# stepdrv.net
KiCad netlist of a schematic drawn in EAGLE
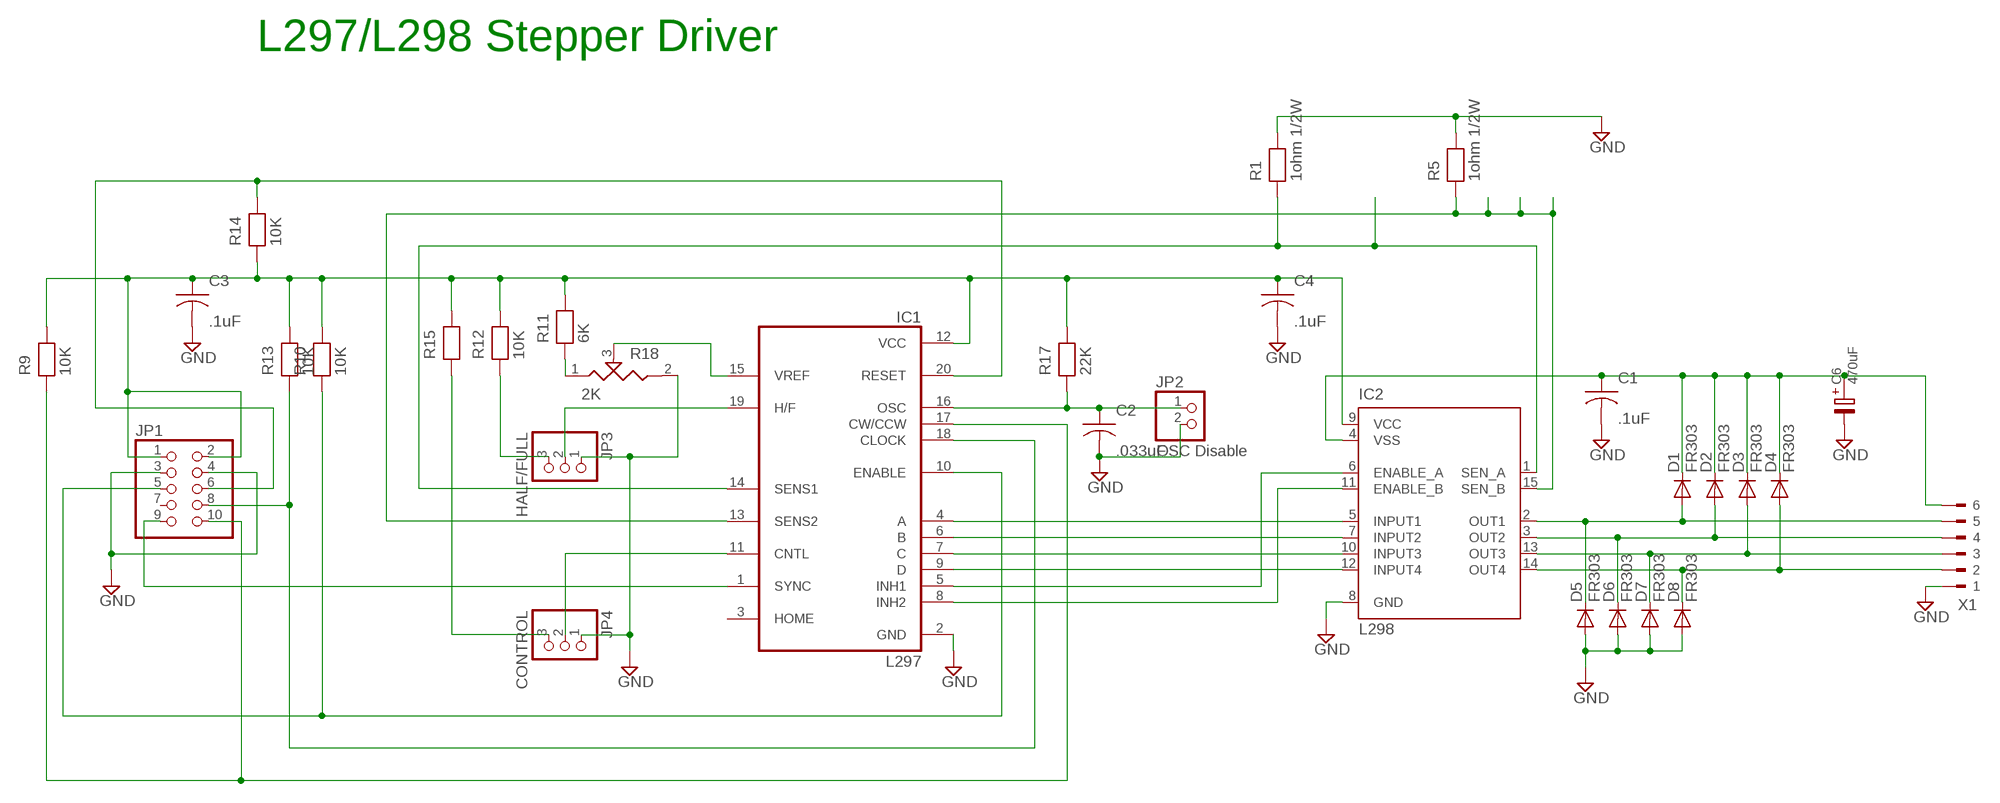
[diagram p0: schematic, sheet 1]

(export (version "E")
  (design (tool "Eeschema 10.0.6"))
  (components
    (comp (ref "C1")
      (value ".1uF")
      (footprint "eagle-import:C-5")
      (libsource (lib "eagle-import") (part "CAP-5"))
    )
    (comp (ref "C2")
      (value ".033uF")
      (footprint "eagle-import:C-5")
      (libsource (lib "eagle-import") (part "CAP-5"))
    )
    (comp (ref "C3")
      (value ".1uF")
      (footprint "eagle-import:C-5")
      (libsource (lib "eagle-import") (part "CAP-5"))
    )
    (comp (ref "C4")
      (value ".1uF")
      (footprint "eagle-import:C-5")
      (libsource (lib "eagle-import") (part "CAP-5"))
    )
    (comp (ref "C6")
      (value "470uF")
      (footprint "eagle-import:E5,0-12")
      (libsource (lib "eagle-import") (part "E5,0-12"))
    )
    (comp (ref "D1")
      (value "FR303")
      (footprint "eagle-import:DO201-15")
      (libsource (lib "eagle-import") (part "DIODE-DO201-15"))
    )
    (comp (ref "D2")
      (value "FR303")
      (footprint "eagle-import:DO201-15")
      (libsource (lib "eagle-import") (part "DIODE-DO201-15"))
    )
    (comp (ref "D3")
      (value "FR303")
      (footprint "eagle-import:DO201-15")
      (libsource (lib "eagle-import") (part "DIODE-DO201-15"))
    )
    (comp (ref "D4")
      (value "FR303")
      (footprint "eagle-import:DO201-15")
      (libsource (lib "eagle-import") (part "DIODE-DO201-15"))
    )
    (comp (ref "D5")
      (value "FR303")
      (footprint "eagle-import:DO201-15")
      (libsource (lib "eagle-import") (part "DIODE-DO201-15"))
    )
    (comp (ref "D6")
      (value "FR303")
      (footprint "eagle-import:DO201-15")
      (libsource (lib "eagle-import") (part "DIODE-DO201-15"))
    )
    (comp (ref "D7")
      (value "FR303")
      (footprint "eagle-import:DO201-15")
      (libsource (lib "eagle-import") (part "DIODE-DO201-15"))
    )
    (comp (ref "D8")
      (value "FR303")
      (footprint "eagle-import:DO201-15")
      (libsource (lib "eagle-import") (part "DIODE-DO201-15"))
    )
    (comp (ref "IC1")
      (value "L297")
      (footprint "eagle-import:DIL20")
      (libsource (lib "eagle-import") (part "L297"))
    )
    (comp (ref "IC2")
      (value "L298")
      (footprint "eagle-import:MULTIWATT-15")
      (libsource (lib "eagle-import") (part "L298"))
    )
    (comp (ref "JP1")
      (value "PINHD-2X5")
      (footprint "eagle-import:2X05")
      (libsource (lib "eagle-import") (part "PINHD-2X5"))
    )
    (comp (ref "JP2")
      (value "OSC Disable")
      (footprint "eagle-import:1X02")
      (libsource (lib "eagle-import") (part "PINHD-1X2"))
    )
    (comp (ref "JP3")
      (value "HALF/FULL")
      (footprint "eagle-import:1X03")
      (libsource (lib "eagle-import") (part "PINHD-1X3"))
    )
    (comp (ref "JP4")
      (value "CONTROL")
      (footprint "eagle-import:1X03")
      (libsource (lib "eagle-import") (part "PINHD-1X3"))
    )
    (comp (ref "R1")
      (value "1ohm 1/2W")
      (footprint "eagle-import:R-12,5")
      (libsource (lib "eagle-import") (part "RESEU-12,5"))
    )
    (comp (ref "R5")
      (value "1ohm 1/2W")
      (footprint "eagle-import:R-12,5")
      (libsource (lib "eagle-import") (part "RESEU-12,5"))
    )
    (comp (ref "R9")
      (value "10K")
      (footprint "eagle-import:R-10")
      (libsource (lib "eagle-import") (part "RESEU-10"))
    )
    (comp (ref "R10")
      (value "10K")
      (footprint "eagle-import:R-10")
      (libsource (lib "eagle-import") (part "RESEU-10"))
    )
    (comp (ref "R11")
      (value "6K")
      (footprint "eagle-import:R-10")
      (libsource (lib "eagle-import") (part "RESEU-10"))
    )
    (comp (ref "R12")
      (value "10K")
      (footprint "eagle-import:R-10")
      (libsource (lib "eagle-import") (part "RESEU-10"))
    )
    (comp (ref "R13")
      (value "10K")
      (footprint "eagle-import:R-10")
      (libsource (lib "eagle-import") (part "RESEU-10"))
    )
    (comp (ref "R14")
      (value "10K")
      (footprint "eagle-import:R-10")
      (libsource (lib "eagle-import") (part "RESEU-10"))
    )
    (comp (ref "R15")
      (value "RESEU-10")
      (footprint "eagle-import:R-10")
      (libsource (lib "eagle-import") (part "RESEU-10"))
    )
    (comp (ref "R17")
      (value "22K")
      (footprint "eagle-import:R-10")
      (libsource (lib "eagle-import") (part "RESEU-10"))
    )
    (comp (ref "R18")
      (value "2K")
      (footprint "eagle-import:PT-10S")
      (libsource (lib "eagle-import") (part "POTUS-S"))
    )
    (comp (ref "X1")
      (value "90-6")
      (footprint "eagle-import:90-6")
      (libsource (lib "eagle-import") (part "90-6"))
    )
  )
  (nets
    (net (code "1") (name "GND") (class "Default")
      (node (ref "C1") (pin "2") (pinfunction "2_2") (pintype "passive"))
      (node (ref "C2") (pin "2") (pinfunction "2_2") (pintype "passive"))
      (node (ref "C3") (pin "2") (pinfunction "2_2") (pintype "passive"))
      (node (ref "C4") (pin "2") (pinfunction "2_2") (pintype "passive"))
      (node (ref "C6") (pin "-") (pinfunction "-_-") (pintype "passive"))
      (node (ref "D5") (pin "A") (pinfunction "A_A") (pintype "passive"))
      (node (ref "D6") (pin "A") (pinfunction "A_A") (pintype "passive"))
      (node (ref "D7") (pin "A") (pinfunction "A_A") (pintype "passive"))
      (node (ref "D8") (pin "A") (pinfunction "A_A") (pintype "passive"))
      (node (ref "IC1") (pin "2") (pinfunction "GND_2") (pintype "power_in"))
      (node (ref "IC2") (pin "8") (pinfunction "GND_8") (pintype "power_in"))
      (node (ref "JP1") (pin "3") (pinfunction "3_3") (pintype "passive"))
      (node (ref "JP1") (pin "4") (pinfunction "4_4") (pintype "passive"))
      (node (ref "JP2") (pin "2") (pinfunction "2_2") (pintype "passive"))
      (node (ref "JP3") (pin "1") (pinfunction "1_1") (pintype "passive"))
      (node (ref "JP4") (pin "1") (pinfunction "1_1") (pintype "passive"))
      (node (ref "R1") (pin "2") (pinfunction "2_2") (pintype "passive"))
      (node (ref "R18") (pin "2") (pinfunction "2_2") (pintype "passive"))
      (node (ref "R5") (pin "2") (pinfunction "2_2") (pintype "passive"))
      (node (ref "X1") (pin "1") (pinfunction "1_1") (pintype "passive"))
    )
    (net (code "2") (name "Net-(IC1-A)") (class "Default")
      (node (ref "IC1") (pin "4") (pinfunction "A_4") (pintype "output"))
      (node (ref "IC2") (pin "5") (pinfunction "INPUT1_5") (pintype "input"))
    )
    (net (code "3") (name "Net-(IC1-B)") (class "Default")
      (node (ref "IC1") (pin "6") (pinfunction "B_6") (pintype "output"))
      (node (ref "IC2") (pin "7") (pinfunction "INPUT2_7") (pintype "input"))
    )
    (net (code "4") (name "Net-(IC1-C)") (class "Default")
      (node (ref "IC1") (pin "7") (pinfunction "C_7") (pintype "output"))
      (node (ref "IC2") (pin "10") (pinfunction "INPUT3_10") (pintype "input"))
    )
    (net (code "5") (name "Net-(IC1-CLOCK)") (class "Default")
      (node (ref "IC1") (pin "18") (pinfunction "CLOCK_18") (pintype "input"))
      (node (ref "JP1") (pin "8") (pinfunction "8_8") (pintype "passive"))
      (node (ref "R13") (pin "1") (pinfunction "1_1") (pintype "passive"))
    )
    (net (code "6") (name "Net-(IC1-CNTL)") (class "Default")
      (node (ref "IC1") (pin "11") (pinfunction "CNTL_11") (pintype "input"))
      (node (ref "JP4") (pin "2") (pinfunction "2_2") (pintype "passive"))
    )
    (net (code "7") (name "Net-(IC1-CW{slash}CCW)") (class "Default")
      (node (ref "IC1") (pin "17") (pinfunction "CW/CCW_17") (pintype "input"))
      (node (ref "JP1") (pin "10") (pinfunction "10_10") (pintype "passive"))
      (node (ref "R9") (pin "1") (pinfunction "1_1") (pintype "passive"))
    )
    (net (code "8") (name "Net-(IC1-D)") (class "Default")
      (node (ref "IC1") (pin "9") (pinfunction "D_9") (pintype "output"))
      (node (ref "IC2") (pin "12") (pinfunction "INPUT4_12") (pintype "input"))
    )
    (net (code "9") (name "Net-(IC1-ENABLE)") (class "Default")
      (node (ref "IC1") (pin "10") (pinfunction "ENABLE_10") (pintype "input"))
      (node (ref "JP1") (pin "5") (pinfunction "5_5") (pintype "passive"))
      (node (ref "R10") (pin "1") (pinfunction "1_1") (pintype "passive"))
    )
    (net (code "10") (name "Net-(IC1-H{slash}F)") (class "Default")
      (node (ref "IC1") (pin "19") (pinfunction "H/F_19") (pintype "input"))
      (node (ref "JP3") (pin "2") (pinfunction "2_2") (pintype "passive"))
    )
    (net (code "11") (name "Net-(IC1-INH1)") (class "Default")
      (node (ref "IC1") (pin "5") (pinfunction "INH1_5") (pintype "output"))
      (node (ref "IC2") (pin "6") (pinfunction "ENABLE_A_6") (pintype "input"))
    )
    (net (code "12") (name "Net-(IC1-INH2)") (class "Default")
      (node (ref "IC1") (pin "8") (pinfunction "INH2_8") (pintype "output"))
      (node (ref "IC2") (pin "11") (pinfunction "ENABLE_B_11") (pintype "input"))
    )
    (net (code "13") (name "Net-(IC1-OSC)") (class "Default")
      (node (ref "C2") (pin "1") (pinfunction "1_1") (pintype "passive"))
      (node (ref "IC1") (pin "16") (pinfunction "OSC_16") (pintype "bidirectional"))
      (node (ref "JP2") (pin "1") (pinfunction "1_1") (pintype "passive"))
      (node (ref "R17") (pin "1") (pinfunction "1_1") (pintype "passive"))
    )
    (net (code "14") (name "Net-(IC1-RESET)") (class "Default")
      (node (ref "IC1") (pin "20") (pinfunction "RESET_20") (pintype "input"))
      (node (ref "JP1") (pin "6") (pinfunction "6_6") (pintype "passive"))
      (node (ref "R14") (pin "2") (pinfunction "2_2") (pintype "passive"))
    )
    (net (code "15") (name "Net-(IC1-SENS1)") (class "Default")
      (node (ref "IC1") (pin "14") (pinfunction "SENS1_14") (pintype "output"))
      (node (ref "IC2") (pin "1") (pinfunction "SEN_A_1") (pintype "input"))
      (node (ref "R1") (pin "1") (pinfunction "1_1") (pintype "passive"))
    )
    (net (code "16") (name "Net-(IC1-SENS2)") (class "Default")
      (node (ref "IC1") (pin "13") (pinfunction "SENS2_13") (pintype "output"))
      (node (ref "IC2") (pin "15") (pinfunction "SEN_B_15") (pintype "input"))
      (node (ref "R5") (pin "1") (pinfunction "1_1") (pintype "passive"))
    )
    (net (code "17") (name "Net-(IC1-SYNC)") (class "Default")
      (node (ref "IC1") (pin "1") (pinfunction "SYNC_1") (pintype "output"))
      (node (ref "JP1") (pin "9") (pinfunction "9_9") (pintype "passive"))
    )
    (net (code "18") (name "Net-(IC1-VCC)") (class "Default")
      (node (ref "C3") (pin "1") (pinfunction "1_1") (pintype "passive"))
      (node (ref "C4") (pin "1") (pinfunction "1_1") (pintype "passive"))
      (node (ref "IC1") (pin "12") (pinfunction "VCC_12") (pintype "power_in"))
      (node (ref "IC2") (pin "9") (pinfunction "VCC_9") (pintype "power_in"))
      (node (ref "JP1") (pin "1") (pinfunction "1_1") (pintype "passive"))
      (node (ref "JP1") (pin "2") (pinfunction "2_2") (pintype "passive"))
      (node (ref "R10") (pin "2") (pinfunction "2_2") (pintype "passive"))
      (node (ref "R11") (pin "2") (pinfunction "2_2") (pintype "passive"))
      (node (ref "R12") (pin "2") (pinfunction "2_2") (pintype "passive"))
      (node (ref "R13") (pin "2") (pinfunction "2_2") (pintype "passive"))
      (node (ref "R14") (pin "1") (pinfunction "1_1") (pintype "passive"))
      (node (ref "R15") (pin "2") (pinfunction "2_2") (pintype "passive"))
      (node (ref "R17") (pin "2") (pinfunction "2_2") (pintype "passive"))
      (node (ref "R9") (pin "2") (pinfunction "2_2") (pintype "passive"))
    )
    (net (code "19") (name "Net-(IC1-VREF)") (class "Default")
      (node (ref "IC1") (pin "15") (pinfunction "VREF_15") (pintype "input"))
      (node (ref "R18") (pin "3") (pinfunction "3_3") (pintype "passive"))
    )
    (net (code "20") (name "Net-(IC2-OUT1)") (class "Default")
      (node (ref "D1") (pin "A") (pinfunction "A_A") (pintype "passive"))
      (node (ref "D5") (pin "C") (pinfunction "C_C") (pintype "passive"))
      (node (ref "IC2") (pin "2") (pinfunction "OUT1_2") (pintype "output"))
      (node (ref "X1") (pin "5") (pinfunction "5_5") (pintype "passive"))
    )
    (net (code "21") (name "Net-(IC2-OUT2)") (class "Default")
      (node (ref "D2") (pin "A") (pinfunction "A_A") (pintype "passive"))
      (node (ref "D6") (pin "C") (pinfunction "C_C") (pintype "passive"))
      (node (ref "IC2") (pin "3") (pinfunction "OUT2_3") (pintype "output"))
      (node (ref "X1") (pin "4") (pinfunction "4_4") (pintype "passive"))
    )
    (net (code "22") (name "Net-(IC2-OUT3)") (class "Default")
      (node (ref "D3") (pin "A") (pinfunction "A_A") (pintype "passive"))
      (node (ref "D7") (pin "C") (pinfunction "C_C") (pintype "passive"))
      (node (ref "IC2") (pin "13") (pinfunction "OUT3_13") (pintype "output"))
      (node (ref "X1") (pin "3") (pinfunction "3_3") (pintype "passive"))
    )
    (net (code "23") (name "Net-(IC2-OUT4)") (class "Default")
      (node (ref "D4") (pin "A") (pinfunction "A_A") (pintype "passive"))
      (node (ref "D8") (pin "C") (pinfunction "C_C") (pintype "passive"))
      (node (ref "IC2") (pin "14") (pinfunction "OUT4_14") (pintype "output"))
      (node (ref "X1") (pin "2") (pinfunction "2_2") (pintype "passive"))
    )
    (net (code "24") (name "Net-(IC2-VSS)") (class "Default")
      (node (ref "C1") (pin "1") (pinfunction "1_1") (pintype "passive"))
      (node (ref "C6") (pin "+") (pinfunction "+_+") (pintype "passive"))
      (node (ref "D1") (pin "C") (pinfunction "C_C") (pintype "passive"))
      (node (ref "D2") (pin "C") (pinfunction "C_C") (pintype "passive"))
      (node (ref "D3") (pin "C") (pinfunction "C_C") (pintype "passive"))
      (node (ref "D4") (pin "C") (pinfunction "C_C") (pintype "passive"))
      (node (ref "IC2") (pin "4") (pinfunction "VSS_4") (pintype "power_in"))
      (node (ref "X1") (pin "6") (pinfunction "6_6") (pintype "passive"))
    )
    (net (code "25") (name "Net-(JP3-Pad3)") (class "Default")
      (node (ref "JP3") (pin "3") (pinfunction "3_3") (pintype "passive"))
      (node (ref "R12") (pin "1") (pinfunction "1_1") (pintype "passive"))
    )
    (net (code "26") (name "Net-(JP4-Pad3)") (class "Default")
      (node (ref "JP4") (pin "3") (pinfunction "3_3") (pintype "passive"))
      (node (ref "R15") (pin "1") (pinfunction "1_1") (pintype "passive"))
    )
    (net (code "27") (name "Net-(R11-Pad1)") (class "Default")
      (node (ref "R11") (pin "1") (pinfunction "1_1") (pintype "passive"))
      (node (ref "R18") (pin "1") (pinfunction "1_1") (pintype "passive"))
    )
    (net (code "28") (name "unconnected-(IC1-HOME-Pad3)") (class "Default")
      (node (ref "IC1") (pin "3") (pinfunction "HOME_3") (pintype "output"))
    )
    (net (code "29") (name "unconnected-(JP1-Pad7)") (class "Default")
      (node (ref "JP1") (pin "7") (pinfunction "7_7") (pintype "passive"))
    )
  )
)
